# lab5_sriley.net
KiCad netlist of a schematic drawn in EAGLE
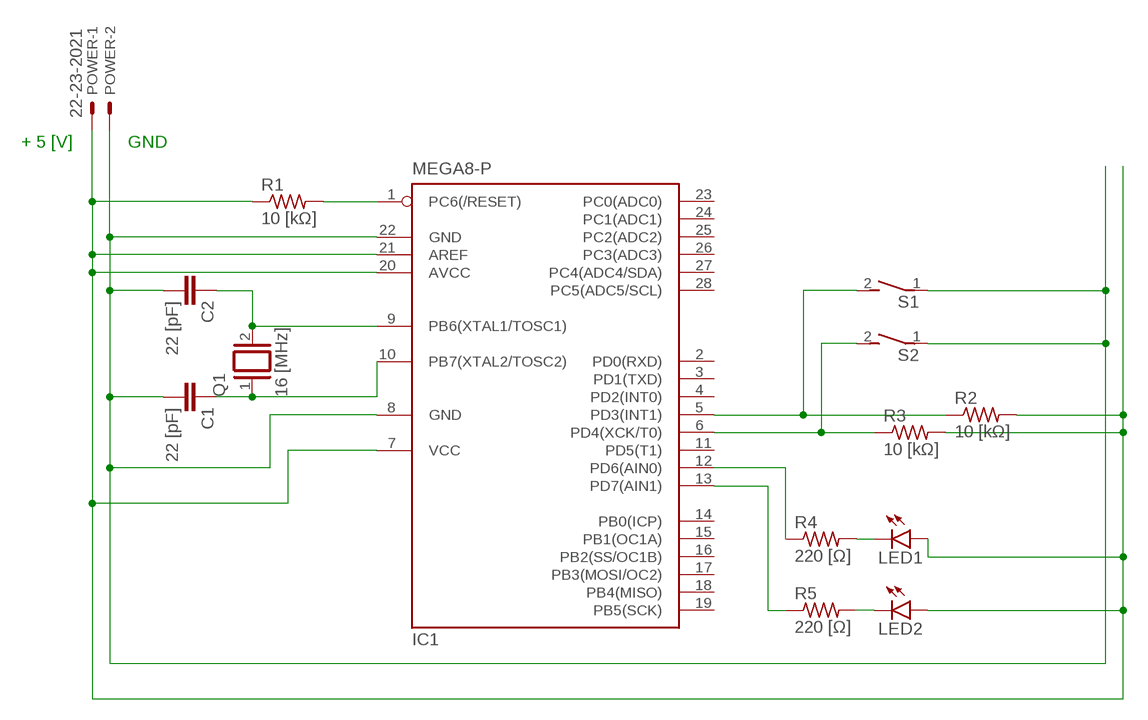
[diagram p0: schematic, sheet 1]

(export (version "E")
  (design (tool "Eeschema 10.0.6"))
  (components
    (comp (ref "C1")
      (value "22 [pF]")
      (footprint "eagle-import:C2.5-3")
      (libsource (lib "eagle-import") (part "C2,5-3"))
    )
    (comp (ref "C2")
      (value "22 [pF]")
      (footprint "eagle-import:C2.5-3")
      (libsource (lib "eagle-import") (part "C2,5-3"))
    )
    (comp (ref "IC1")
      (value "MEGA8-P")
      (footprint "eagle-import:DIL28-3")
      (libsource (lib "eagle-import") (part "MEGA8-P"))
    )
    (comp (ref "LED1")
      (value "LED5MM")
      (footprint "eagle-import:LED5MM")
      (libsource (lib "eagle-import") (part "LED5MM"))
    )
    (comp (ref "LED2")
      (value "LED5MM")
      (footprint "eagle-import:LED5MM")
      (libsource (lib "eagle-import") (part "LED5MM"))
    )
    (comp (ref "POWER")
      (value "22-23-2021")
      (footprint "eagle-import:22-23-2021")
      (fields (field (name "MF") "MOLEX"))
      (libsource (lib "eagle-import") (part "22-23-2021"))
    )
    (comp (ref "Q1")
      (value "16 [MHz]")
      (footprint "eagle-import:Q")
      (libsource (lib "eagle-import") (part "XTAL"))
    )
    (comp (ref "R1")
      (value "10 [kΩ]")
      (footprint "eagle-import:0204_7")
      (libsource (lib "eagle-import") (part "R-US_0204/7"))
    )
    (comp (ref "R2")
      (value "10 [kΩ]")
      (footprint "eagle-import:0204_7")
      (libsource (lib "eagle-import") (part "R-US_0204/7"))
    )
    (comp (ref "R3")
      (value "10 [kΩ]")
      (footprint "eagle-import:0204_7")
      (libsource (lib "eagle-import") (part "R-US_0204/7"))
    )
    (comp (ref "R4")
      (value "220 [Ω]")
      (footprint "eagle-import:0204_7")
      (libsource (lib "eagle-import") (part "R-US_0204/7"))
    )
    (comp (ref "R5")
      (value "220 [Ω]")
      (footprint "eagle-import:0204_7")
      (libsource (lib "eagle-import") (part "R-US_0204/7"))
    )
    (comp (ref "S1")
      (value "DS01E")
      (footprint "eagle-import:DS-01")
      (libsource (lib "eagle-import") (part "DS01E"))
    )
    (comp (ref "S2")
      (value "DS01E")
      (footprint "eagle-import:DS-01")
      (libsource (lib "eagle-import") (part "DS01E"))
    )
  )
  (nets
    (net (code "1") (name "Net-(IC1-AREF)") (class "Default")
      (node (ref "IC1") (pin "20") (pinfunction "AVCC_20") (pintype "power_in"))
      (node (ref "IC1") (pin "21") (pinfunction "AREF_21") (pintype "passive"))
      (node (ref "IC1") (pin "7") (pinfunction "VCC_7") (pintype "power_in"))
      (node (ref "LED1") (pin "A") (pinfunction "A_A") (pintype "passive"))
      (node (ref "LED2") (pin "A") (pinfunction "A_A") (pintype "passive"))
      (node (ref "POWER") (pin "1") (pinfunction "S_1") (pintype "passive"))
      (node (ref "R1") (pin "1") (pinfunction "1_1") (pintype "passive"))
      (node (ref "R2") (pin "2") (pinfunction "2_2") (pintype "passive"))
      (node (ref "R3") (pin "2") (pinfunction "2_2") (pintype "passive"))
    )
    (net (code "2") (name "Net-(IC1-PB6(XTAL1{slash}TOSC1))") (class "Default")
      (node (ref "C2") (pin "1") (pinfunction "1_1") (pintype "passive"))
      (node (ref "IC1") (pin "9") (pinfunction "PB6(XTAL1/TOSC1)_9") (pintype "bidirectional"))
      (node (ref "Q1") (pin "2") (pinfunction "2_2") (pintype "passive"))
    )
    (net (code "3") (name "Net-(IC1-PB7(XTAL2{slash}TOSC2))") (class "Default")
      (node (ref "C1") (pin "1") (pinfunction "1_1") (pintype "passive"))
      (node (ref "IC1") (pin "10") (pinfunction "PB7(XTAL2/TOSC2)_10") (pintype "bidirectional"))
      (node (ref "Q1") (pin "1") (pinfunction "1_1") (pintype "passive"))
    )
    (net (code "4") (name "Net-(IC1-PC6({slash}RESET))") (class "Default")
      (node (ref "IC1") (pin "1") (pinfunction "PC6(/RESET)_1") (pintype "bidirectional"))
      (node (ref "R1") (pin "2") (pinfunction "2_2") (pintype "passive"))
    )
    (net (code "5") (name "Net-(IC1-PD3(INT1))") (class "Default")
      (node (ref "IC1") (pin "5") (pinfunction "PD3(INT1)_5") (pintype "bidirectional"))
      (node (ref "R2") (pin "1") (pinfunction "1_1") (pintype "passive"))
      (node (ref "S1") (pin "2") (pinfunction "2_2") (pintype "passive"))
    )
    (net (code "6") (name "Net-(IC1-PD4(XCK{slash}T0))") (class "Default")
      (node (ref "IC1") (pin "6") (pinfunction "PD4(XCK/T0)_6") (pintype "bidirectional"))
      (node (ref "R3") (pin "1") (pinfunction "1_1") (pintype "passive"))
      (node (ref "S2") (pin "2") (pinfunction "2_2") (pintype "passive"))
    )
    (net (code "7") (name "Net-(IC1-PD6(AIN0))") (class "Default")
      (node (ref "IC1") (pin "12") (pinfunction "PD6(AIN0)_12") (pintype "bidirectional"))
      (node (ref "R4") (pin "1") (pinfunction "1_1") (pintype "passive"))
    )
    (net (code "8") (name "Net-(IC1-PD7(AIN1))") (class "Default")
      (node (ref "IC1") (pin "13") (pinfunction "PD7(AIN1)_13") (pintype "bidirectional"))
      (node (ref "R5") (pin "1") (pinfunction "1_1") (pintype "passive"))
    )
    (net (code "9") (name "Net-(LED1-C)") (class "Default")
      (node (ref "LED1") (pin "K") (pinfunction "C_K") (pintype "passive"))
      (node (ref "R4") (pin "2") (pinfunction "2_2") (pintype "passive"))
    )
    (net (code "10") (name "Net-(LED2-C)") (class "Default")
      (node (ref "LED2") (pin "K") (pinfunction "C_K") (pintype "passive"))
      (node (ref "R5") (pin "2") (pinfunction "2_2") (pintype "passive"))
    )
    (net (code "11") (name "Net-(POWERB-S)") (class "Default")
      (node (ref "C1") (pin "2") (pinfunction "2_2") (pintype "passive"))
      (node (ref "C2") (pin "2") (pinfunction "2_2") (pintype "passive"))
      (node (ref "IC1") (pin "22") (pinfunction "GND_22") (pintype "power_in"))
      (node (ref "IC1") (pin "8") (pinfunction "GND_8") (pintype "power_in"))
      (node (ref "POWER") (pin "2") (pinfunction "S_2") (pintype "passive"))
      (node (ref "S1") (pin "1") (pinfunction "1_1") (pintype "passive"))
      (node (ref "S2") (pin "1") (pinfunction "1_1") (pintype "passive"))
    )
    (net (code "12") (name "unconnected-(IC1-PB0(ICP)-Pad14)") (class "Default")
      (node (ref "IC1") (pin "14") (pinfunction "PB0(ICP)_14") (pintype "bidirectional"))
    )
    (net (code "13") (name "unconnected-(IC1-PB1(OC1A)-Pad15)") (class "Default")
      (node (ref "IC1") (pin "15") (pinfunction "PB1(OC1A)_15") (pintype "bidirectional"))
    )
    (net (code "14") (name "unconnected-(IC1-PB2(SS{slash}OC1B)-Pad16)") (class "Default")
      (node (ref "IC1") (pin "16") (pinfunction "PB2(SS/OC1B)_16") (pintype "bidirectional"))
    )
    (net (code "15") (name "unconnected-(IC1-PB3(MOSI{slash}OC2)-Pad17)") (class "Default")
      (node (ref "IC1") (pin "17") (pinfunction "PB3(MOSI/OC2)_17") (pintype "bidirectional"))
    )
    (net (code "16") (name "unconnected-(IC1-PB4(MISO)-Pad18)") (class "Default")
      (node (ref "IC1") (pin "18") (pinfunction "PB4(MISO)_18") (pintype "bidirectional"))
    )
    (net (code "17") (name "unconnected-(IC1-PB5(SCK)-Pad19)") (class "Default")
      (node (ref "IC1") (pin "19") (pinfunction "PB5(SCK)_19") (pintype "bidirectional"))
    )
    (net (code "18") (name "unconnected-(IC1-PC0(ADC0)-Pad23)") (class "Default")
      (node (ref "IC1") (pin "23") (pinfunction "PC0(ADC0)_23") (pintype "bidirectional"))
    )
    (net (code "19") (name "unconnected-(IC1-PC1(ADC1)-Pad24)") (class "Default")
      (node (ref "IC1") (pin "24") (pinfunction "PC1(ADC1)_24") (pintype "bidirectional"))
    )
    (net (code "20") (name "unconnected-(IC1-PC2(ADC2)-Pad25)") (class "Default")
      (node (ref "IC1") (pin "25") (pinfunction "PC2(ADC2)_25") (pintype "bidirectional"))
    )
    (net (code "21") (name "unconnected-(IC1-PC3(ADC3)-Pad26)") (class "Default")
      (node (ref "IC1") (pin "26") (pinfunction "PC3(ADC3)_26") (pintype "bidirectional"))
    )
    (net (code "22") (name "unconnected-(IC1-PC4(ADC4{slash}SDA)-Pad27)") (class "Default")
      (node (ref "IC1") (pin "27") (pinfunction "PC4(ADC4/SDA)_27") (pintype "bidirectional"))
    )
    (net (code "23") (name "unconnected-(IC1-PC5(ADC5{slash}SCL)-Pad28)") (class "Default")
      (node (ref "IC1") (pin "28") (pinfunction "PC5(ADC5/SCL)_28") (pintype "bidirectional"))
    )
    (net (code "24") (name "unconnected-(IC1-PD0(RXD)-Pad2)") (class "Default")
      (node (ref "IC1") (pin "2") (pinfunction "PD0(RXD)_2") (pintype "bidirectional"))
    )
    (net (code "25") (name "unconnected-(IC1-PD1(TXD)-Pad3)") (class "Default")
      (node (ref "IC1") (pin "3") (pinfunction "PD1(TXD)_3") (pintype "bidirectional"))
    )
    (net (code "26") (name "unconnected-(IC1-PD2(INT0)-Pad4)") (class "Default")
      (node (ref "IC1") (pin "4") (pinfunction "PD2(INT0)_4") (pintype "bidirectional"))
    )
    (net (code "27") (name "unconnected-(IC1-PD5(T1)-Pad11)") (class "Default")
      (node (ref "IC1") (pin "11") (pinfunction "PD5(T1)_11") (pintype "bidirectional"))
    )
  )
)
